# RatRig_-_EVA_-_Board.net
KiCad netlist of a schematic drawn in EAGLE
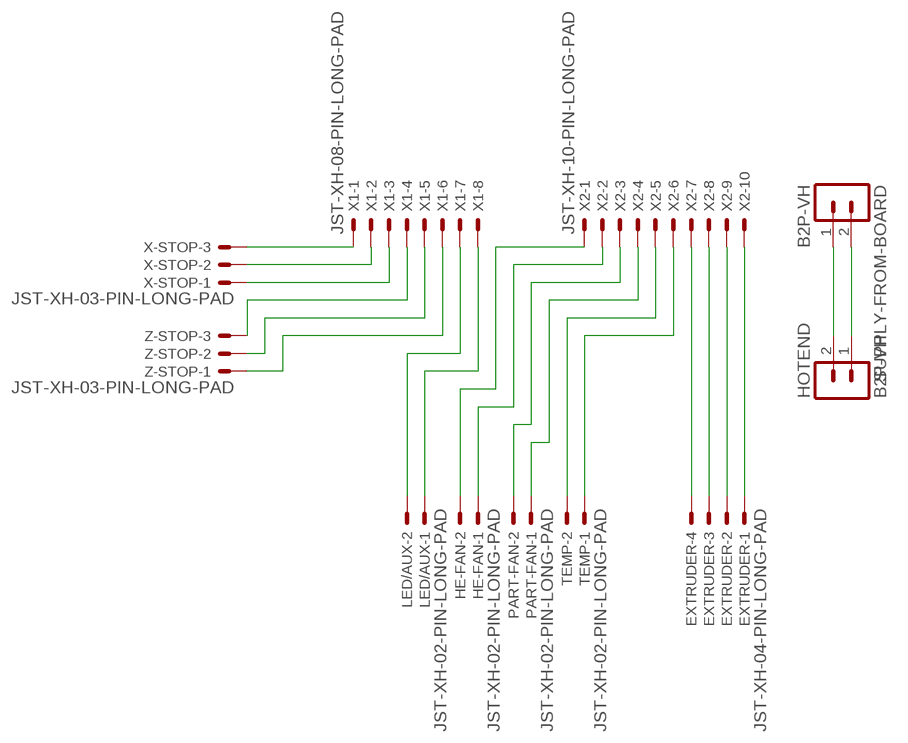
[diagram p0: schematic, sheet 1]

(export (version "E")
  (design (tool "Eeschema 10.0.6"))
  (components
    (comp (ref "EXTRUDER")
      (value "JST-XH-04-PIN-LONG-PAD")
      (footprint "eagle-import:JST-XH-04-PACKAGE-LONG-PAD")
      (libsource (lib "eagle-import") (part "JST-XH-04-PIN-LONG-PAD"))
    )
    (comp (ref "HE-FAN")
      (value "JST-XH-02-PIN-LONG-PAD")
      (footprint "eagle-import:JST-XH-02-PACKAGE-LONG-PAD")
      (libsource (lib "eagle-import") (part "JST-XH-02-PIN-LONG-PAD"))
    )
    (comp (ref "HOTEND")
      (value "B2P-VH")
      (footprint "eagle-import:B2P-VH")
      (libsource (lib "eagle-import") (part "B2P-VH"))
    )
    (comp (ref "LED/AUX")
      (value "JST-XH-02-PIN-LONG-PAD")
      (footprint "eagle-import:JST-XH-02-PACKAGE-LONG-PAD")
      (libsource (lib "eagle-import") (part "JST-XH-02-PIN-LONG-PAD"))
    )
    (comp (ref "PART-FAN")
      (value "JST-XH-02-PIN-LONG-PAD")
      (footprint "eagle-import:JST-XH-02-PACKAGE-LONG-PAD")
      (libsource (lib "eagle-import") (part "JST-XH-02-PIN-LONG-PAD"))
    )
    (comp (ref "SUPPLY-FROM-BOARD")
      (value "B2P-VH")
      (footprint "eagle-import:B2P-VH")
      (libsource (lib "eagle-import") (part "B2P-VH"))
    )
    (comp (ref "TEMP")
      (value "JST-XH-02-PIN-LONG-PAD")
      (footprint "eagle-import:JST-XH-02-PACKAGE-LONG-PAD")
      (libsource (lib "eagle-import") (part "JST-XH-02-PIN-LONG-PAD"))
    )
    (comp (ref "X-STOP")
      (value "JST-XH-03-PIN-LONG-PAD")
      (footprint "eagle-import:JST-XH-03-PACKAGE-LONG-PAD")
      (libsource (lib "eagle-import") (part "JST-XH-03-PIN-LONG-PAD"))
    )
    (comp (ref "X1")
      (value "JST-XH-08-PIN-LONG-PAD")
      (footprint "eagle-import:JST-XH-08-PACKAGE-LONG-PAD")
      (libsource (lib "eagle-import") (part "JST-XH-08-PIN-LONG-PAD"))
    )
    (comp (ref "X2")
      (value "JST-XH-10-PIN-LONG-PAD")
      (footprint "eagle-import:JST-XH-10-PACKAGE-LONG-PAD")
      (libsource (lib "eagle-import") (part "JST-XH-10-PIN-LONG-PAD"))
    )
    (comp (ref "Z-STOP")
      (value "JST-XH-03-PIN-LONG-PAD")
      (footprint "eagle-import:JST-XH-03-PACKAGE-LONG-PAD")
      (libsource (lib "eagle-import") (part "JST-XH-03-PIN-LONG-PAD"))
    )
  )
  (nets
    (net (code "1") (name "Net-(EXTRUDERA-S)") (class "Default")
      (node (ref "EXTRUDER") (pin "1") (pinfunction "S_1") (pintype "passive"))
      (node (ref "X2") (pin "10") (pinfunction "S_10") (pintype "passive"))
    )
    (net (code "2") (name "Net-(EXTRUDERB-S)") (class "Default")
      (node (ref "EXTRUDER") (pin "2") (pinfunction "S_2") (pintype "passive"))
      (node (ref "X2") (pin "9") (pinfunction "S_9") (pintype "passive"))
    )
    (net (code "3") (name "Net-(EXTRUDERC-S)") (class "Default")
      (node (ref "EXTRUDER") (pin "3") (pinfunction "S_3") (pintype "passive"))
      (node (ref "X2") (pin "8") (pinfunction "S_8") (pintype "passive"))
    )
    (net (code "4") (name "Net-(EXTRUDERD-S)") (class "Default")
      (node (ref "EXTRUDER") (pin "4") (pinfunction "S_4") (pintype "passive"))
      (node (ref "X2") (pin "7") (pinfunction "S_7") (pintype "passive"))
    )
    (net (code "5") (name "Net-(HE-FANA-S)") (class "Default")
      (node (ref "HE-FAN") (pin "1") (pinfunction "S_1") (pintype "passive"))
      (node (ref "X2") (pin "2") (pinfunction "S_2") (pintype "passive"))
    )
    (net (code "6") (name "Net-(HE-FANB-S)") (class "Default")
      (node (ref "HE-FAN") (pin "2") (pinfunction "S_2") (pintype "passive"))
      (node (ref "X2") (pin "1") (pinfunction "S_1") (pintype "passive"))
    )
    (net (code "7") (name "Net-(HOTEND-Pad1)") (class "Default")
      (node (ref "HOTEND") (pin "1") (pinfunction "1_1") (pintype "passive"))
      (node (ref "SUPPLY-FROM-BOARD") (pin "2") (pinfunction "2_2") (pintype "passive"))
    )
    (net (code "8") (name "Net-(HOTEND-Pad2)") (class "Default")
      (node (ref "HOTEND") (pin "2") (pinfunction "2_2") (pintype "passive"))
      (node (ref "SUPPLY-FROM-BOARD") (pin "1") (pinfunction "1_1") (pintype "passive"))
    )
    (net (code "9") (name "Net-(LED/AUXA-S)") (class "Default")
      (node (ref "LED/AUX") (pin "1") (pinfunction "S_1") (pintype "passive"))
      (node (ref "X1") (pin "8") (pinfunction "S_8") (pintype "passive"))
    )
    (net (code "10") (name "Net-(LED/AUXB-S)") (class "Default")
      (node (ref "LED/AUX") (pin "2") (pinfunction "S_2") (pintype "passive"))
      (node (ref "X1") (pin "7") (pinfunction "S_7") (pintype "passive"))
    )
    (net (code "11") (name "Net-(PART-FANA-S)") (class "Default")
      (node (ref "PART-FAN") (pin "1") (pinfunction "S_1") (pintype "passive"))
      (node (ref "X2") (pin "4") (pinfunction "S_4") (pintype "passive"))
    )
    (net (code "12") (name "Net-(PART-FANB-S)") (class "Default")
      (node (ref "PART-FAN") (pin "2") (pinfunction "S_2") (pintype "passive"))
      (node (ref "X2") (pin "3") (pinfunction "S_3") (pintype "passive"))
    )
    (net (code "13") (name "Net-(TEMPA-S)") (class "Default")
      (node (ref "TEMP") (pin "1") (pinfunction "S_1") (pintype "passive"))
      (node (ref "X2") (pin "6") (pinfunction "S_6") (pintype "passive"))
    )
    (net (code "14") (name "Net-(TEMPB-S)") (class "Default")
      (node (ref "TEMP") (pin "2") (pinfunction "S_2") (pintype "passive"))
      (node (ref "X2") (pin "5") (pinfunction "S_5") (pintype "passive"))
    )
    (net (code "15") (name "Net-(X-STOPA-S)") (class "Default")
      (node (ref "X-STOP") (pin "1") (pinfunction "S_1") (pintype "passive"))
      (node (ref "X1") (pin "3") (pinfunction "S_3") (pintype "passive"))
    )
    (net (code "16") (name "Net-(X-STOPB-S)") (class "Default")
      (node (ref "X-STOP") (pin "2") (pinfunction "S_2") (pintype "passive"))
      (node (ref "X1") (pin "2") (pinfunction "S_2") (pintype "passive"))
    )
    (net (code "17") (name "Net-(X-STOPC-S)") (class "Default")
      (node (ref "X-STOP") (pin "3") (pinfunction "S_3") (pintype "passive"))
      (node (ref "X1") (pin "1") (pinfunction "S_1") (pintype "passive"))
    )
    (net (code "18") (name "Net-(X1D-S)") (class "Default")
      (node (ref "X1") (pin "4") (pinfunction "S_4") (pintype "passive"))
      (node (ref "Z-STOP") (pin "3") (pinfunction "S_3") (pintype "passive"))
    )
    (net (code "19") (name "Net-(X1E-S)") (class "Default")
      (node (ref "X1") (pin "5") (pinfunction "S_5") (pintype "passive"))
      (node (ref "Z-STOP") (pin "2") (pinfunction "S_2") (pintype "passive"))
    )
    (net (code "20") (name "Net-(X1F-S)") (class "Default")
      (node (ref "X1") (pin "6") (pinfunction "S_6") (pintype "passive"))
      (node (ref "Z-STOP") (pin "1") (pinfunction "S_1") (pintype "passive"))
    )
  )
)
